# sch_camera2.net
KiCad netlist of a schematic drawn in Altium Designer
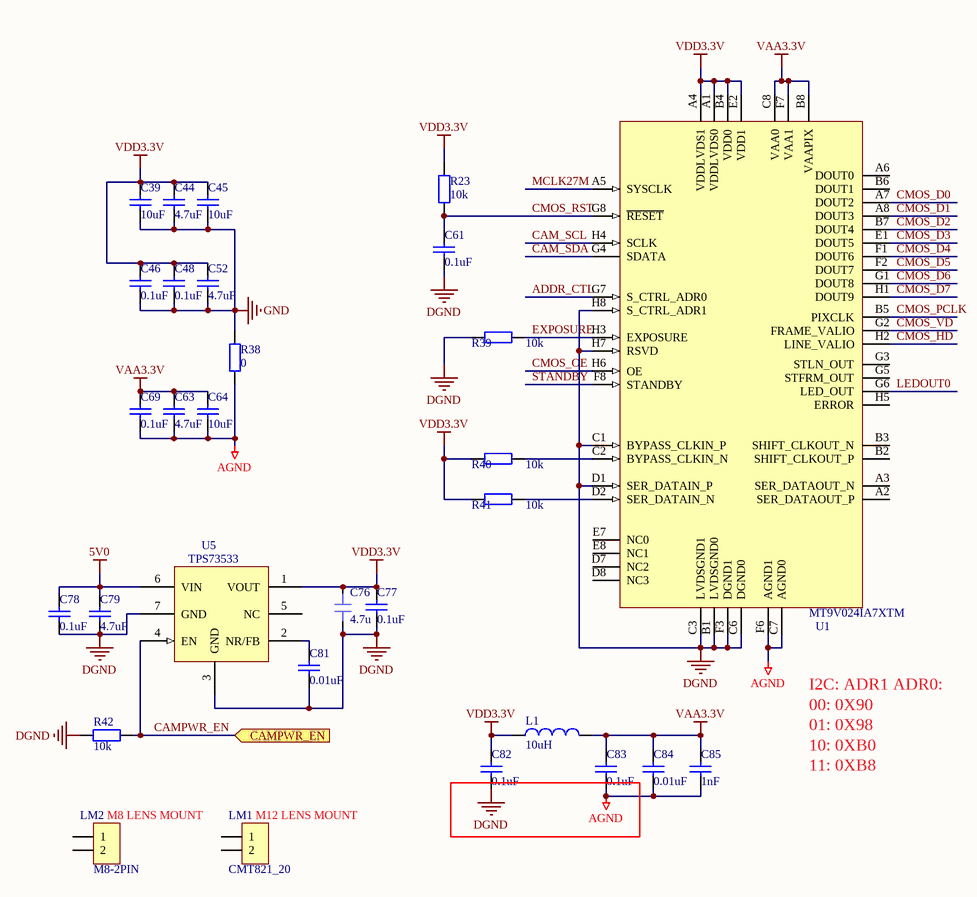
[diagram p0: sch_camera2.SchDoc]

(export (version "E")
  (design (tool "Eeschema 10.0.6"))
  (components
    (comp (ref "C39")
      (value "10uF")
      (footprint "0805C")
      (description "Capacitor")
      (fields (field (name "PUBLISHER") "Altium Limited"))
      (libsource (lib "Miscellaneous Devices") (part "Cap"))
    )
    (comp (ref "C44")
      (value "4.7uF")
      (footprint "0402C")
      (description "Capacitor")
      (fields (field (name "PUBLISHER") "Altium Limited"))
      (libsource (lib "Miscellaneous Devices") (part "Cap"))
    )
    (comp (ref "C45")
      (value "10uF")
      (footprint "0805C")
      (description "Capacitor")
      (fields (field (name "PUBLISHER") "Altium Limited"))
      (libsource (lib "Miscellaneous Devices") (part "Cap"))
    )
    (comp (ref "C46")
      (value "0.1uF")
      (footprint "0402C")
      (description "Capacitor")
      (fields (field (name "PUBLISHER") "Altium Limited"))
      (libsource (lib "Miscellaneous Devices") (part "Cap"))
    )
    (comp (ref "C48")
      (value "0.1uF")
      (footprint "0402C")
      (description "Capacitor")
      (fields (field (name "PUBLISHER") "Altium Limited"))
      (libsource (lib "Miscellaneous Devices") (part "Cap"))
    )
    (comp (ref "C52")
      (value "4.7uF")
      (footprint "0402C")
      (description "Capacitor")
      (fields (field (name "PUBLISHER") "Altium Limited"))
      (libsource (lib "Miscellaneous Devices") (part "Cap"))
    )
    (comp (ref "C61")
      (value "0.1uF")
      (footprint "0402C")
      (description "Capacitor")
      (fields (field (name "PUBLISHER") "Altium Limited"))
      (libsource (lib "Miscellaneous Devices") (part "Cap"))
    )
    (comp (ref "C63")
      (value "4.7uF")
      (footprint "0402C")
      (description "Capacitor")
      (fields (field (name "PUBLISHER") "Altium Limited"))
      (libsource (lib "Miscellaneous Devices") (part "Cap"))
    )
    (comp (ref "C64")
      (value "10uF")
      (footprint "0805C")
      (description "Capacitor")
      (fields (field (name "PUBLISHER") "Altium Limited"))
      (libsource (lib "Miscellaneous Devices") (part "Cap"))
    )
    (comp (ref "C69")
      (value "0.1uF")
      (footprint "0402C")
      (description "Capacitor")
      (fields (field (name "PUBLISHER") "Altium Limited"))
      (libsource (lib "Miscellaneous Devices") (part "Cap"))
    )
    (comp (ref "C76")
      (value "4.7u")
      (footprint "0402C_L")
      (description "CC0402MRX5R5BB475")
      (libsource (lib "V0P1") (part "cap0402"))
    )
    (comp (ref "C77")
      (value "0.1uF")
      (footprint "0402C_L")
      (description "Capacitor")
      (fields (field (name "PUBLISHER") "Altium Limited"))
      (libsource (lib "Miscellaneous Devices") (part "Cap"))
    )
    (comp (ref "C78")
      (value "0.1uF")
      (footprint "0402C")
      (description "Capacitor")
      (fields (field (name "PUBLISHER") "Altium Limited"))
      (libsource (lib "Miscellaneous Devices") (part "Cap"))
    )
    (comp (ref "C79")
      (value "4.7uF")
      (footprint "0402C_L")
      (description "Capacitor")
      (fields (field (name "PUBLISHER") "Altium Limited"))
      (libsource (lib "Miscellaneous Devices") (part "Cap"))
    )
    (comp (ref "C81")
      (value "0.01uF")
      (footprint "0402C_L")
      (description "Capacitor")
      (fields (field (name "PUBLISHER") "Altium Limited"))
      (libsource (lib "Miscellaneous Devices") (part "Cap"))
    )
    (comp (ref "C82")
      (value "0.1uF")
      (footprint "0402C_L")
      (description "Capacitor")
      (fields (field (name "PUBLISHER") "Altium Limited"))
      (libsource (lib "Miscellaneous Devices") (part "Cap"))
    )
    (comp (ref "C83")
      (value "0.1uF")
      (footprint "0402C_L")
      (description "Capacitor")
      (fields (field (name "PUBLISHER") "Altium Limited"))
      (libsource (lib "Miscellaneous Devices") (part "Cap"))
    )
    (comp (ref "C84")
      (value "0.01uF")
      (footprint "0402C_L")
      (description "Capacitor")
      (fields (field (name "PUBLISHER") "Altium Limited"))
      (libsource (lib "Miscellaneous Devices") (part "Cap"))
    )
    (comp (ref "C85")
      (value "1nF")
      (footprint "0402C_L")
      (description "Capacitor")
      (fields (field (name "PUBLISHER") "Altium Limited"))
      (libsource (lib "Miscellaneous Devices") (part "Cap"))
    )
    (comp (ref "L1")
      (value "10uH")
      (footprint "0805R")
      (description "Inductor")
      (libsource (lib "SWUST_ROBOT") (part "Inductor"))
    )
    (comp (ref "LM1")
      (value "CMT821_20")
      (footprint "PAD_M3_D350_450")
      (description "Connector")
      (libsource (lib "SuperSchLib") (part "CON2"))
    )
    (comp (ref "LM2")
      (value "M8-2PIN")
      (footprint "PAD_M3_D350_450")
      (description "Connector")
      (libsource (lib "SuperSchLib") (part "CON2"))
    )
    (comp (ref "R23")
      (value "10k")
      (footprint "0402R")
      (description "Resistor")
      (fields (field (name "Comment") "10K") (field (name "PUBLISHER") "Altium Limited"))
      (libsource (lib "SZG") (part "Resistor"))
    )
    (comp (ref "R38")
      (value "0")
      (footprint "0402R")
      (description "Resistor")
      (fields (field (name "Comment") "0R") (field (name "PUBLISHER") "Altium Limited"))
      (libsource (lib "") (part "Resistor_3"))
    )
    (comp (ref "R39")
      (value "10k")
      (footprint "0402R")
      (description "Resistor")
      (fields (field (name "Comment") "10K") (field (name "PUBLISHER") "Altium Limited"))
      (libsource (lib "") (part "Resistor_1"))
    )
    (comp (ref "R40")
      (value "10k")
      (footprint "0402R")
      (description "Resistor")
      (fields (field (name "Comment") "10K") (field (name "PUBLISHER") "Altium Limited"))
      (libsource (lib "") (part "Resistor_1"))
    )
    (comp (ref "R41")
      (value "10k")
      (footprint "0402R")
      (description "Resistor")
      (fields (field (name "Comment") "10K") (field (name "PUBLISHER") "Altium Limited"))
      (libsource (lib "") (part "Resistor_1"))
    )
    (comp (ref "R42")
      (value "10k")
      (footprint "0402R_L")
      (description "Resistor")
      (fields (field (name "Comment") "10K") (field (name "PUBLISHER") "Altium Limited"))
      (libsource (lib "") (part "Resistor_2"))
    )
    (comp (ref "U1")
      (value "MT9V024IA7XTM")
      (footprint "IBGA52_8X8_P100L90W90H90R")
      (libsource (lib "SZG") (part "MT9V024IA7XTM"))
    )
    (comp (ref "U5")
      (value "TPS73533")
      (footprint "SON6_P65L21W21H8_DRV")
      (libsource (lib "SZG") (part "TPS73533"))
    )
  )
  (nets
    (net (code "1") (name "/ADDR_CTL") (class "Default")
      (node (ref "U1") (pin "G7") (pinfunction "S_CTRL_ADR0_G7") (pintype "input"))
    )
    (net (code "2") (name "/CAMPWR_EN") (class "Default")
      (node (ref "R42") (pin "2") (pinfunction "2_2") (pintype "passive"))
      (node (ref "U5") (pin "4") (pinfunction "EN_4") (pintype "input"))
    )
    (net (code "3") (name "/CAM_SCL") (class "Default")
      (node (ref "U1") (pin "H4") (pinfunction "SCLK_H4") (pintype "input"))
    )
    (net (code "4") (name "/CAM_SDA") (class "Default")
      (node (ref "U1") (pin "G4") (pinfunction "SDATA_G4") (pintype "passive"))
    )
    (net (code "5") (name "/CMOS_D0") (class "Default")
      (node (ref "U1") (pin "A7") (pinfunction "DOUT2_A7") (pintype "passive"))
    )
    (net (code "6") (name "/CMOS_D1") (class "Default")
      (node (ref "U1") (pin "A8") (pinfunction "DOUT3_A8") (pintype "passive"))
    )
    (net (code "7") (name "/CMOS_D2") (class "Default")
      (node (ref "U1") (pin "B7") (pinfunction "DOUT4_B7") (pintype "passive"))
    )
    (net (code "8") (name "/CMOS_D3") (class "Default")
      (node (ref "U1") (pin "E1") (pinfunction "DOUT5_E1") (pintype "passive"))
    )
    (net (code "9") (name "/CMOS_D4") (class "Default")
      (node (ref "U1") (pin "F1") (pinfunction "DOUT6_F1") (pintype "passive"))
    )
    (net (code "10") (name "/CMOS_D5") (class "Default")
      (node (ref "U1") (pin "F2") (pinfunction "DOUT7_F2") (pintype "passive"))
    )
    (net (code "11") (name "/CMOS_D6") (class "Default")
      (node (ref "U1") (pin "G1") (pinfunction "DOUT8_G1") (pintype "passive"))
    )
    (net (code "12") (name "/CMOS_D7") (class "Default")
      (node (ref "U1") (pin "H1") (pinfunction "DOUT9_H1") (pintype "passive"))
    )
    (net (code "13") (name "/CMOS_HD") (class "Default")
      (node (ref "U1") (pin "H2") (pinfunction "LINE_VALIO_H2") (pintype "passive"))
    )
    (net (code "14") (name "/CMOS_OE") (class "Default")
      (node (ref "U1") (pin "H6") (pinfunction "OE_H6") (pintype "input"))
    )
    (net (code "15") (name "/CMOS_PCLK") (class "Default")
      (node (ref "U1") (pin "B5") (pinfunction "PIXCLK_B5") (pintype "passive"))
    )
    (net (code "16") (name "/CMOS_RST") (class "Default")
      (node (ref "C61") (pin "2") (pinfunction "2_2") (pintype "passive"))
      (node (ref "R23") (pin "1") (pinfunction "1_1") (pintype "passive"))
      (node (ref "U1") (pin "G8") (pinfunction "~{RESET}_G8") (pintype "input"))
    )
    (net (code "17") (name "/CMOS_VD") (class "Default")
      (node (ref "U1") (pin "G2") (pinfunction "FRAME_VALIO_G2") (pintype "passive"))
    )
    (net (code "18") (name "/EXPOSURE") (class "Default")
      (node (ref "R39") (pin "1") (pinfunction "1_1") (pintype "passive"))
      (node (ref "U1") (pin "H3") (pinfunction "EXPOSURE_H3") (pintype "input"))
    )
    (net (code "19") (name "/LEDOUT0") (class "Default")
      (node (ref "U1") (pin "G6") (pinfunction "LED_OUT_G6") (pintype "passive"))
    )
    (net (code "20") (name "/MCLK27M") (class "Default")
      (node (ref "U1") (pin "A5") (pinfunction "SYSCLK_A5") (pintype "input"))
    )
    (net (code "21") (name "/STANDBY") (class "Default")
      (node (ref "U1") (pin "F8") (pinfunction "STANDBY_F8") (pintype "input"))
    )
    (net (code "22") (name "5V0") (class "Default")
      (node (ref "C78") (pin "2") (pinfunction "2_2") (pintype "passive"))
      (node (ref "C79") (pin "2") (pinfunction "2_2") (pintype "passive"))
      (node (ref "U5") (pin "6") (pinfunction "VIN_6") (pintype "passive"))
    )
    (net (code "23") (name "AGND") (class "Default")
      (node (ref "C63") (pin "1") (pinfunction "1_1") (pintype "passive"))
      (node (ref "C64") (pin "1") (pinfunction "1_1") (pintype "passive"))
      (node (ref "C69") (pin "1") (pinfunction "1_1") (pintype "passive"))
      (node (ref "C83") (pin "1") (pinfunction "1_1") (pintype "passive"))
      (node (ref "C84") (pin "1") (pinfunction "1_1") (pintype "passive"))
      (node (ref "C85") (pin "1") (pinfunction "1_1") (pintype "passive"))
      (node (ref "R38") (pin "2") (pinfunction "2_2") (pintype "passive"))
      (node (ref "U1") (pin "C7") (pinfunction "AGND0_C7") (pintype "power_in"))
      (node (ref "U1") (pin "F6") (pinfunction "AGND1_F6") (pintype "power_in"))
    )
    (net (code "24") (name "DGND") (class "Default")
      (node (ref "C61") (pin "1") (pinfunction "1_1") (pintype "passive"))
      (node (ref "C76") (pin "2") (pinfunction "2_2") (pintype "passive"))
      (node (ref "C77") (pin "1") (pinfunction "1_1") (pintype "passive"))
      (node (ref "C78") (pin "1") (pinfunction "1_1") (pintype "passive"))
      (node (ref "C79") (pin "1") (pinfunction "1_1") (pintype "passive"))
      (node (ref "C81") (pin "1") (pinfunction "1_1") (pintype "passive"))
      (node (ref "C82") (pin "1") (pinfunction "1_1") (pintype "passive"))
      (node (ref "R39") (pin "2") (pinfunction "2_2") (pintype "passive"))
      (node (ref "R42") (pin "1") (pinfunction "1_1") (pintype "passive"))
      (node (ref "U1") (pin "B1") (pinfunction "LVDSGND0_B1") (pintype "power_in"))
      (node (ref "U1") (pin "C1") (pinfunction "BYPASS_CLKIN_P_C1") (pintype "input"))
      (node (ref "U1") (pin "C3") (pinfunction "LVDSGND1_C3") (pintype "power_in"))
      (node (ref "U1") (pin "C6") (pinfunction "DGND0_C6") (pintype "power_in"))
      (node (ref "U1") (pin "D1") (pinfunction "SER_DATAIN_P_D1") (pintype "input"))
      (node (ref "U1") (pin "F3") (pinfunction "DGND1_F3") (pintype "power_in"))
      (node (ref "U1") (pin "H7") (pinfunction "RSVD_H7") (pintype "input"))
      (node (ref "U1") (pin "H8") (pinfunction "S_CTRL_ADR1_H8") (pintype "input"))
      (node (ref "U5") (pin "3") (pinfunction "GND_3") (pintype "passive"))
      (node (ref "U5") (pin "7") (pinfunction "GND_7") (pintype "passive"))
    )
    (net (code "25") (name "GND") (class "Default")
      (node (ref "C39") (pin "1") (pinfunction "1_1") (pintype "passive"))
      (node (ref "C44") (pin "1") (pinfunction "1_1") (pintype "passive"))
      (node (ref "C45") (pin "1") (pinfunction "1_1") (pintype "passive"))
      (node (ref "C46") (pin "1") (pinfunction "1_1") (pintype "passive"))
      (node (ref "C48") (pin "1") (pinfunction "1_1") (pintype "passive"))
      (node (ref "C52") (pin "1") (pinfunction "1_1") (pintype "passive"))
      (node (ref "R38") (pin "1") (pinfunction "1_1") (pintype "passive"))
    )
    (net (code "26") (name "Net-(U1-BYPASS_CLKIN_N)") (class "Default")
      (node (ref "R40") (pin "1") (pinfunction "1_1") (pintype "passive"))
      (node (ref "U1") (pin "C2") (pinfunction "BYPASS_CLKIN_N_C2") (pintype "input"))
    )
    (net (code "27") (name "Net-(U1-SER_DATAIN_N)") (class "Default")
      (node (ref "R41") (pin "1") (pinfunction "1_1") (pintype "passive"))
      (node (ref "U1") (pin "D2") (pinfunction "SER_DATAIN_N_D2") (pintype "input"))
    )
    (net (code "28") (name "Net-(U5-NR{slash}FB)") (class "Default")
      (node (ref "C81") (pin "2") (pinfunction "2_2") (pintype "passive"))
      (node (ref "U5") (pin "2") (pinfunction "NR/FB_2") (pintype "passive"))
    )
    (net (code "29") (name "VAA3.3V") (class "Default")
      (node (ref "C63") (pin "2") (pinfunction "2_2") (pintype "passive"))
      (node (ref "C64") (pin "2") (pinfunction "2_2") (pintype "passive"))
      (node (ref "C69") (pin "2") (pinfunction "2_2") (pintype "passive"))
      (node (ref "C83") (pin "2") (pinfunction "2_2") (pintype "passive"))
      (node (ref "C84") (pin "2") (pinfunction "2_2") (pintype "passive"))
      (node (ref "C85") (pin "2") (pinfunction "2_2") (pintype "passive"))
      (node (ref "L1") (pin "2") (pinfunction "2_2") (pintype "passive"))
      (node (ref "U1") (pin "B8") (pinfunction "VAAPIX_B8") (pintype "power_in"))
      (node (ref "U1") (pin "C8") (pinfunction "VAA0_C8") (pintype "power_in"))
      (node (ref "U1") (pin "F7") (pinfunction "VAA1_F7") (pintype "power_in"))
    )
    (net (code "30") (name "VDD3.3V") (class "Default")
      (node (ref "C39") (pin "2") (pinfunction "2_2") (pintype "passive"))
      (node (ref "C44") (pin "2") (pinfunction "2_2") (pintype "passive"))
      (node (ref "C45") (pin "2") (pinfunction "2_2") (pintype "passive"))
      (node (ref "C46") (pin "2") (pinfunction "2_2") (pintype "passive"))
      (node (ref "C48") (pin "2") (pinfunction "2_2") (pintype "passive"))
      (node (ref "C52") (pin "2") (pinfunction "2_2") (pintype "passive"))
      (node (ref "C76") (pin "1") (pinfunction "1_1") (pintype "passive"))
      (node (ref "C77") (pin "2") (pinfunction "2_2") (pintype "passive"))
      (node (ref "C82") (pin "2") (pinfunction "2_2") (pintype "passive"))
      (node (ref "L1") (pin "1") (pinfunction "1_1") (pintype "passive"))
      (node (ref "R23") (pin "2") (pinfunction "2_2") (pintype "passive"))
      (node (ref "R40") (pin "2") (pinfunction "2_2") (pintype "passive"))
      (node (ref "R41") (pin "2") (pinfunction "2_2") (pintype "passive"))
      (node (ref "U1") (pin "A1") (pinfunction "VDDLVDS0_A1") (pintype "power_in"))
      (node (ref "U1") (pin "A4") (pinfunction "VDDLVDS1_A4") (pintype "power_in"))
      (node (ref "U1") (pin "B4") (pinfunction "VDD0_B4") (pintype "power_in"))
      (node (ref "U1") (pin "E2") (pinfunction "VDD1_E2") (pintype "power_in"))
      (node (ref "U5") (pin "1") (pinfunction "VOUT_1") (pintype "passive"))
    )
    (net (code "31") (name "unconnected-(LM1-Pad1)") (class "Default")
      (node (ref "LM1") (pin "1") (pinfunction "1_1") (pintype "passive"))
    )
    (net (code "32") (name "unconnected-(LM1-Pad2)") (class "Default")
      (node (ref "LM1") (pin "2") (pinfunction "2_2") (pintype "passive"))
    )
    (net (code "33") (name "unconnected-(LM2-Pad1)") (class "Default")
      (node (ref "LM2") (pin "1") (pinfunction "1_1") (pintype "passive"))
    )
    (net (code "34") (name "unconnected-(LM2-Pad2)") (class "Default")
      (node (ref "LM2") (pin "2") (pinfunction "2_2") (pintype "passive"))
    )
    (net (code "35") (name "unconnected-(U1-DOUT0-PadA6)") (class "Default")
      (node (ref "U1") (pin "A6") (pinfunction "DOUT0_A6") (pintype "passive"))
    )
    (net (code "36") (name "unconnected-(U1-DOUT1-PadB6)") (class "Default")
      (node (ref "U1") (pin "B6") (pinfunction "DOUT1_B6") (pintype "passive"))
    )
    (net (code "37") (name "unconnected-(U1-ERROR-PadH5)") (class "Default")
      (node (ref "U1") (pin "H5") (pinfunction "ERROR_H5") (pintype "passive"))
    )
    (net (code "38") (name "unconnected-(U1-NC0-PadE7)") (class "Default")
      (node (ref "U1") (pin "E7") (pinfunction "NC0_E7") (pintype "passive"))
    )
    (net (code "39") (name "unconnected-(U1-NC1-PadE8)") (class "Default")
      (node (ref "U1") (pin "E8") (pinfunction "NC1_E8") (pintype "power_in"))
    )
    (net (code "40") (name "unconnected-(U1-NC2-PadD7)") (class "Default")
      (node (ref "U1") (pin "D7") (pinfunction "NC2_D7") (pintype "power_in"))
    )
    (net (code "41") (name "unconnected-(U1-NC3-PadD8)") (class "Default")
      (node (ref "U1") (pin "D8") (pinfunction "NC3_D8") (pintype "power_in"))
    )
    (net (code "42") (name "unconnected-(U1-SER_DATAOUT_N-PadA3)") (class "Default")
      (node (ref "U1") (pin "A3") (pinfunction "SER_DATAOUT_N_A3") (pintype "passive"))
    )
    (net (code "43") (name "unconnected-(U1-SER_DATAOUT_P-PadA2)") (class "Default")
      (node (ref "U1") (pin "A2") (pinfunction "SER_DATAOUT_P_A2") (pintype "passive"))
    )
    (net (code "44") (name "unconnected-(U1-SHIFT_CLKOUT_N-PadB3)") (class "Default")
      (node (ref "U1") (pin "B3") (pinfunction "SHIFT_CLKOUT_N_B3") (pintype "passive"))
    )
    (net (code "45") (name "unconnected-(U1-SHIFT_CLKOUT_P-PadB2)") (class "Default")
      (node (ref "U1") (pin "B2") (pinfunction "SHIFT_CLKOUT_P_B2") (pintype "passive"))
    )
    (net (code "46") (name "unconnected-(U1-STFRM_OUT-PadG5)") (class "Default")
      (node (ref "U1") (pin "G5") (pinfunction "STFRM_OUT_G5") (pintype "passive"))
    )
    (net (code "47") (name "unconnected-(U1-STLN_OUT-PadG3)") (class "Default")
      (node (ref "U1") (pin "G3") (pinfunction "STLN_OUT_G3") (pintype "passive"))
    )
    (net (code "48") (name "unconnected-(U5-NC-Pad5)") (class "Default")
      (node (ref "U5") (pin "5") (pinfunction "NC_5") (pintype "passive"))
    )
  )
)
